# Led-button.net
KiCad netlist of a schematic drawn in EAGLE
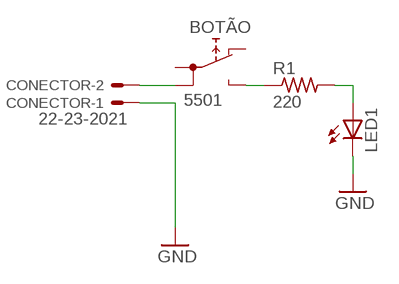
[diagram p0: schematic, sheet 1]

(export (version "E")
  (design (tool "Eeschema 10.0.6"))
  (components
    (comp (ref "BOTÃO")
      (value "5501")
      (footprint "eagle-import:5501")
      (libsource (lib "eagle-import") (part "55?01"))
    )
    (comp (ref "CONECTOR")
      (value "22-23-2021")
      (footprint "eagle-import:22-23-2021")
      (fields (field (name "MF") "MOLEX"))
      (libsource (lib "eagle-import") (part "22-23-2021"))
    )
    (comp (ref "LED1")
      (value "LED5MM")
      (footprint "eagle-import:LED5MM")
      (libsource (lib "eagle-import") (part "LED5MM"))
    )
    (comp (ref "R1")
      (value "220")
      (footprint "eagle-import:0204_7")
      (libsource (lib "eagle-import") (part "R-US_0204/7"))
    )
  )
  (nets
    (net (code "1") (name "GND") (class "Default")
      (node (ref "CONECTOR") (pin "1") (pinfunction "S_1") (pintype "passive"))
      (node (ref "LED1") (pin "K") (pinfunction "C_K") (pintype "passive"))
    )
    (net (code "2") (name "Net-(BOTÃO-PadNO)") (class "Default")
      (node (ref "BOTÃO") (pin "NO") (pinfunction "NO_NO") (pintype "passive"))
      (node (ref "R1") (pin "1") (pinfunction "1_1") (pintype "passive"))
    )
    (net (code "3") (name "Net-(CONECTORB-S)") (class "Default")
      (node (ref "BOTÃO") (pin "1B") (pinfunction "1B_1B") (pintype "passive"))
      (node (ref "CONECTOR") (pin "2") (pinfunction "S_2") (pintype "passive"))
    )
    (net (code "4") (name "Net-(LED1-PadA)") (class "Default")
      (node (ref "LED1") (pin "A") (pinfunction "A_A") (pintype "passive"))
      (node (ref "R1") (pin "2") (pinfunction "2_2") (pintype "passive"))
    )
    (net (code "5") (name "unconnected-(BOTÃO-Pad1A)") (class "Default")
      (node (ref "BOTÃO") (pin "1A") (pinfunction "1A_1A") (pintype "passive"))
    )
    (net (code "6") (name "unconnected-(BOTÃO-PadNC)") (class "Default")
      (node (ref "BOTÃO") (pin "NC") (pinfunction "NC_NC") (pintype "passive"))
    )
  )
)
